# 7segement4digits1badidea-max6958-mk-1_0.net
KiCad netlist of a schematic drawn in EAGLE
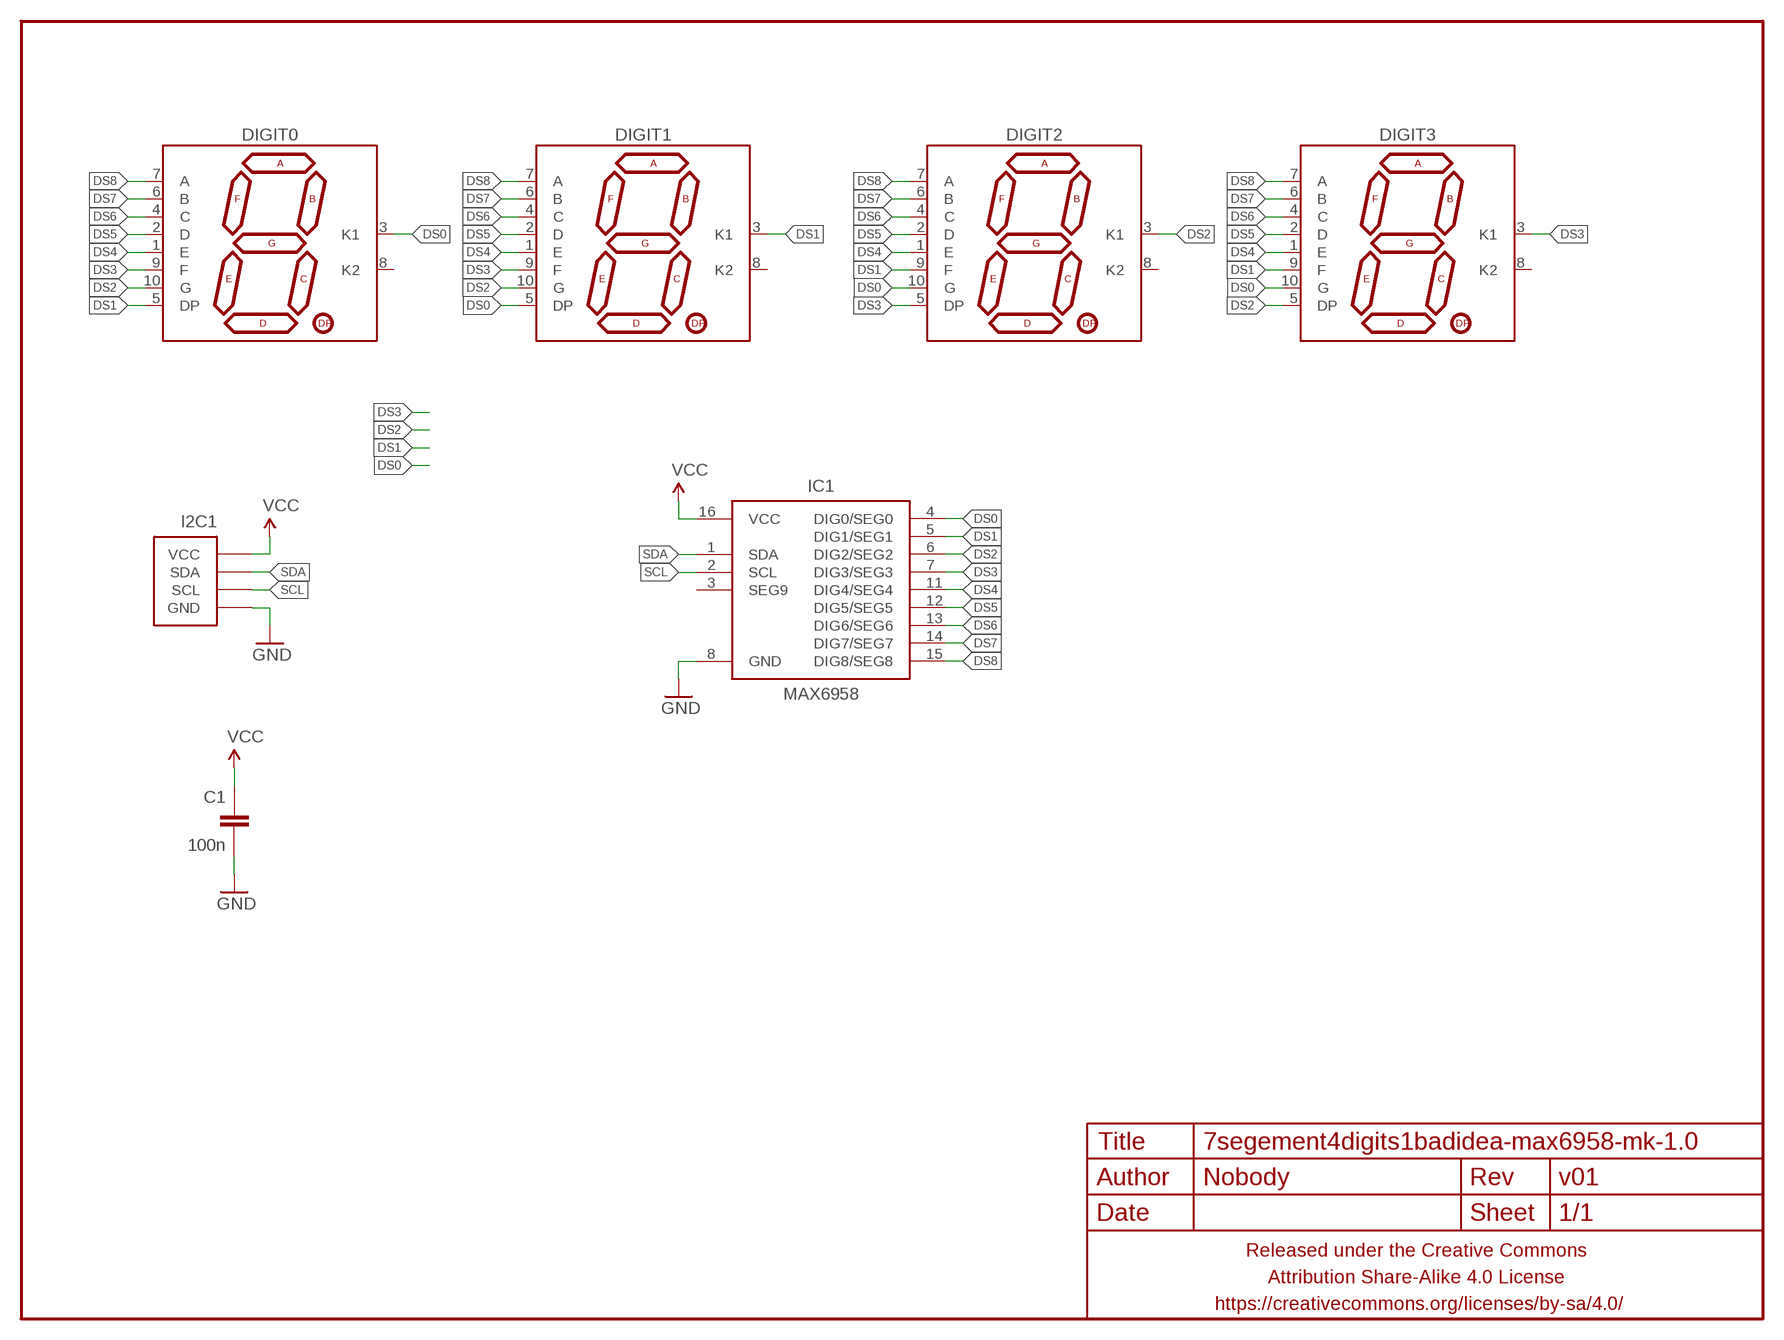
[diagram p0: schematic, sheet 1]

(export (version "E")
  (design (tool "Eeschema 10.0.6"))
  (components
    (comp (ref "C1")
      (value "100n")
      (footprint "eagle-import:C025-024X044")
      (libsource (lib "eagle-import") (part "CAPACITOR-CERAMIC025-024X044"))
    )
    (comp (ref "DIGIT0")
      (value "7SEG_1DIGPTH-25.4MM")
      (footprint "eagle-import:7SEG_1DIG_25.4MM")
      (libsource (lib "eagle-import") (part "7SEG_1DIGPTH-25.4MM"))
    )
    (comp (ref "DIGIT1")
      (value "7SEG_1DIGPTH-25.4MM")
      (footprint "eagle-import:7SEG_1DIG_25.4MM")
      (libsource (lib "eagle-import") (part "7SEG_1DIGPTH-25.4MM"))
    )
    (comp (ref "DIGIT2")
      (value "7SEG_1DIGPTH-25.4MM")
      (footprint "eagle-import:7SEG_1DIG_25.4MM")
      (libsource (lib "eagle-import") (part "7SEG_1DIGPTH-25.4MM"))
    )
    (comp (ref "DIGIT3")
      (value "7SEG_1DIGPTH-25.4MM")
      (footprint "eagle-import:7SEG_1DIG_25.4MM")
      (libsource (lib "eagle-import") (part "7SEG_1DIGPTH-25.4MM"))
    )
    (comp (ref "FRAME1")
      (value "FRAME-LETTERNO_PACKAGE")
      (footprint "eagle-import:DUMMY")
      (fields (field (name "DESIGNER") "Nobody"))
      (libsource (lib "eagle-import") (part "FRAME-LETTERNO_PACKAGE"))
    )
    (comp (ref "I2C1")
      (value "M04-I2CPTH-0.1IN-CENTERED")
      (footprint "eagle-import:1X04-PTH-VERT-I2C-CENTERED")
      (libsource (lib "eagle-import") (part "M04-I2CPTH-0.1IN-CENTERED"))
    )
    (comp (ref "IC1")
      (value "MAX6958")
      (footprint "eagle-import:DIL16")
      (libsource (lib "eagle-import") (part "MAX6958"))
    )
  )
  (nets
    (net (code "1") (name "DS0") (class "Default")
      (node (ref "DIGIT0") (pin "3") (pinfunction "K1_3") (pintype "bidirectional"))
      (node (ref "DIGIT1") (pin "5") (pinfunction "DP_5") (pintype "bidirectional"))
      (node (ref "DIGIT2") (pin "10") (pinfunction "G_10") (pintype "bidirectional"))
      (node (ref "DIGIT3") (pin "10") (pinfunction "G_10") (pintype "bidirectional"))
      (node (ref "IC1") (pin "4") (pinfunction "DIG0/SEG0_4") (pintype "bidirectional"))
    )
    (net (code "2") (name "DS1") (class "Default")
      (node (ref "DIGIT0") (pin "5") (pinfunction "DP_5") (pintype "bidirectional"))
      (node (ref "DIGIT1") (pin "3") (pinfunction "K1_3") (pintype "bidirectional"))
      (node (ref "DIGIT2") (pin "9") (pinfunction "F_9") (pintype "bidirectional"))
      (node (ref "DIGIT3") (pin "9") (pinfunction "F_9") (pintype "bidirectional"))
      (node (ref "IC1") (pin "5") (pinfunction "DIG1/SEG1_5") (pintype "bidirectional"))
    )
    (net (code "3") (name "DS2") (class "Default")
      (node (ref "DIGIT0") (pin "10") (pinfunction "G_10") (pintype "bidirectional"))
      (node (ref "DIGIT1") (pin "10") (pinfunction "G_10") (pintype "bidirectional"))
      (node (ref "DIGIT2") (pin "3") (pinfunction "K1_3") (pintype "bidirectional"))
      (node (ref "DIGIT3") (pin "5") (pinfunction "DP_5") (pintype "bidirectional"))
      (node (ref "IC1") (pin "6") (pinfunction "DIG2/SEG2_6") (pintype "bidirectional"))
    )
    (net (code "4") (name "DS3") (class "Default")
      (node (ref "DIGIT0") (pin "9") (pinfunction "F_9") (pintype "bidirectional"))
      (node (ref "DIGIT1") (pin "9") (pinfunction "F_9") (pintype "bidirectional"))
      (node (ref "DIGIT2") (pin "5") (pinfunction "DP_5") (pintype "bidirectional"))
      (node (ref "DIGIT3") (pin "3") (pinfunction "K1_3") (pintype "bidirectional"))
      (node (ref "IC1") (pin "7") (pinfunction "DIG3/SEG3_7") (pintype "bidirectional"))
    )
    (net (code "5") (name "DS4") (class "Default")
      (node (ref "DIGIT0") (pin "1") (pinfunction "E_1") (pintype "bidirectional"))
      (node (ref "DIGIT1") (pin "1") (pinfunction "E_1") (pintype "bidirectional"))
      (node (ref "DIGIT2") (pin "1") (pinfunction "E_1") (pintype "bidirectional"))
      (node (ref "DIGIT3") (pin "1") (pinfunction "E_1") (pintype "bidirectional"))
      (node (ref "IC1") (pin "11") (pinfunction "DIG4/SEG4_11") (pintype "bidirectional"))
    )
    (net (code "6") (name "DS5") (class "Default")
      (node (ref "DIGIT0") (pin "2") (pinfunction "D_2") (pintype "bidirectional"))
      (node (ref "DIGIT1") (pin "2") (pinfunction "D_2") (pintype "bidirectional"))
      (node (ref "DIGIT2") (pin "2") (pinfunction "D_2") (pintype "bidirectional"))
      (node (ref "DIGIT3") (pin "2") (pinfunction "D_2") (pintype "bidirectional"))
      (node (ref "IC1") (pin "12") (pinfunction "DIG5/SEG5_12") (pintype "bidirectional"))
    )
    (net (code "7") (name "DS6") (class "Default")
      (node (ref "DIGIT0") (pin "4") (pinfunction "C_4") (pintype "bidirectional"))
      (node (ref "DIGIT1") (pin "4") (pinfunction "C_4") (pintype "bidirectional"))
      (node (ref "DIGIT2") (pin "4") (pinfunction "C_4") (pintype "bidirectional"))
      (node (ref "DIGIT3") (pin "4") (pinfunction "C_4") (pintype "bidirectional"))
      (node (ref "IC1") (pin "13") (pinfunction "DIG6/SEG6_13") (pintype "bidirectional"))
    )
    (net (code "8") (name "DS7") (class "Default")
      (node (ref "DIGIT0") (pin "6") (pinfunction "B_6") (pintype "bidirectional"))
      (node (ref "DIGIT1") (pin "6") (pinfunction "B_6") (pintype "bidirectional"))
      (node (ref "DIGIT2") (pin "6") (pinfunction "B_6") (pintype "bidirectional"))
      (node (ref "DIGIT3") (pin "6") (pinfunction "B_6") (pintype "bidirectional"))
      (node (ref "IC1") (pin "14") (pinfunction "DIG7/SEG7_14") (pintype "bidirectional"))
    )
    (net (code "9") (name "DS8") (class "Default")
      (node (ref "DIGIT0") (pin "7") (pinfunction "A_7") (pintype "bidirectional"))
      (node (ref "DIGIT1") (pin "7") (pinfunction "A_7") (pintype "bidirectional"))
      (node (ref "DIGIT2") (pin "7") (pinfunction "A_7") (pintype "bidirectional"))
      (node (ref "DIGIT3") (pin "7") (pinfunction "A_7") (pintype "bidirectional"))
      (node (ref "IC1") (pin "15") (pinfunction "DIG8/SEG8_15") (pintype "bidirectional"))
    )
    (net (code "10") (name "GND") (class "Default")
      (node (ref "C1") (pin "2") (pinfunction "2_2") (pintype "passive"))
      (node (ref "I2C1") (pin "GND") (pinfunction "GND_GND") (pintype "bidirectional"))
      (node (ref "IC1") (pin "8") (pinfunction "GND_8") (pintype "bidirectional"))
    )
    (net (code "11") (name "SCL") (class "Default")
      (node (ref "I2C1") (pin "SCL") (pinfunction "SCL_SCL") (pintype "bidirectional"))
      (node (ref "IC1") (pin "2") (pinfunction "SCL_2") (pintype "bidirectional"))
    )
    (net (code "12") (name "SDA") (class "Default")
      (node (ref "I2C1") (pin "SDA") (pinfunction "SDA_SDA") (pintype "bidirectional"))
      (node (ref "IC1") (pin "1") (pinfunction "SDA_1") (pintype "bidirectional"))
    )
    (net (code "13") (name "VCC") (class "Default")
      (node (ref "C1") (pin "1") (pinfunction "1_1") (pintype "passive"))
      (node (ref "I2C1") (pin "VCC") (pinfunction "VCC_VCC") (pintype "bidirectional"))
      (node (ref "IC1") (pin "16") (pinfunction "VCC_16") (pintype "bidirectional"))
    )
    (net (code "14") (name "unconnected-(DIGIT0-K2-Pad8)") (class "Default")
      (node (ref "DIGIT0") (pin "8") (pinfunction "K2_8") (pintype "bidirectional"))
    )
    (net (code "15") (name "unconnected-(DIGIT1-K2-Pad8)") (class "Default")
      (node (ref "DIGIT1") (pin "8") (pinfunction "K2_8") (pintype "bidirectional"))
    )
    (net (code "16") (name "unconnected-(DIGIT2-K2-Pad8)") (class "Default")
      (node (ref "DIGIT2") (pin "8") (pinfunction "K2_8") (pintype "bidirectional"))
    )
    (net (code "17") (name "unconnected-(DIGIT3-K2-Pad8)") (class "Default")
      (node (ref "DIGIT3") (pin "8") (pinfunction "K2_8") (pintype "bidirectional"))
    )
    (net (code "18") (name "unconnected-(IC1-SEG9-Pad3)") (class "Default")
      (node (ref "IC1") (pin "3") (pinfunction "SEG9_3") (pintype "bidirectional"))
    )
  )
)
